# FT231X_Breakout.net
KiCad netlist of a schematic drawn in EAGLE
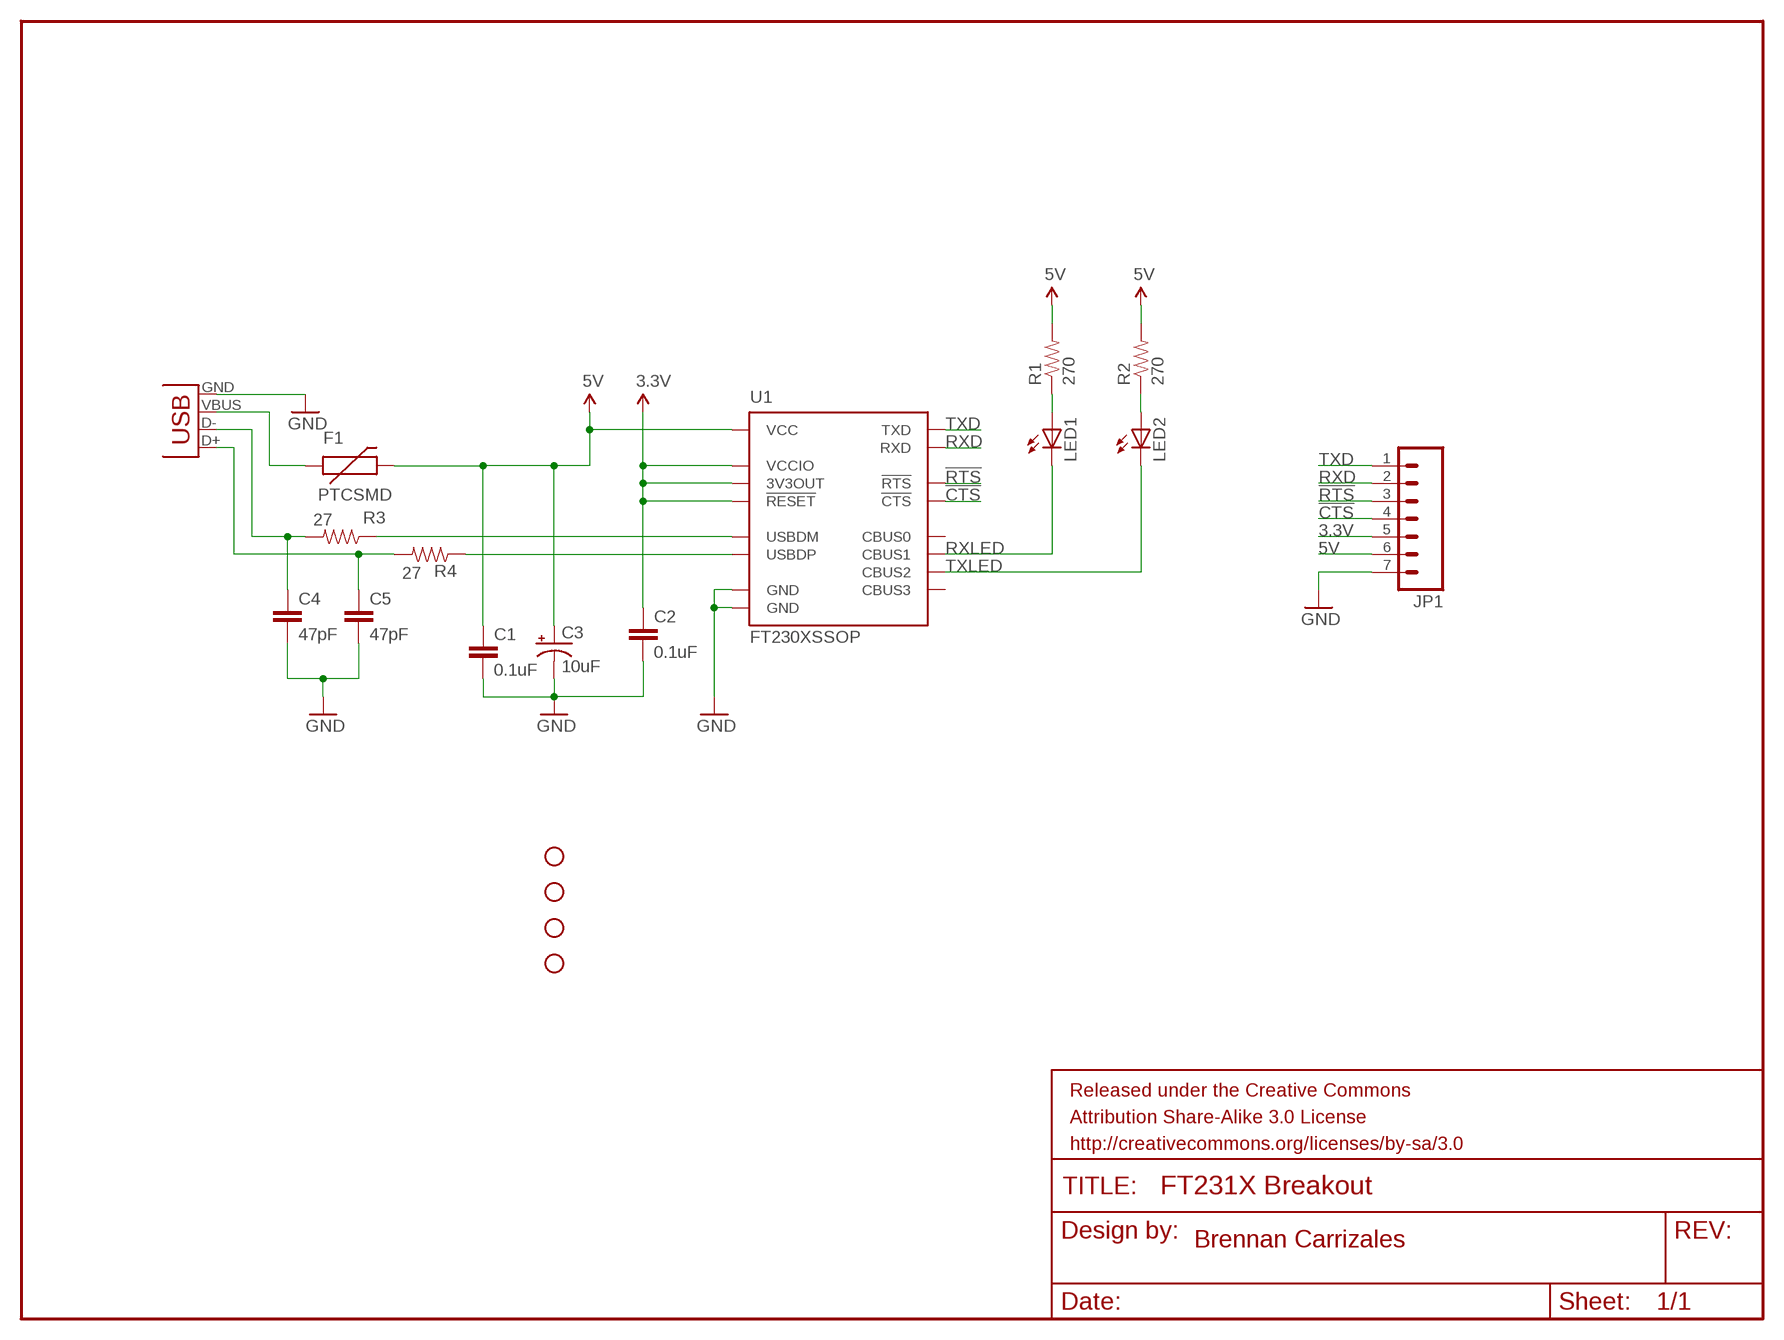
[diagram p0: schematic, sheet 1]

(export (version "E")
  (design (tool "Eeschema 10.0.6"))
  (components
    (comp (ref "C1")
      (value "0.1uF")
      (footprint "eagle-import:0603-CAP")
      (libsource (lib "eagle-import") (part "CAP0603-CAP"))
    )
    (comp (ref "C2")
      (value "0.1uF")
      (footprint "eagle-import:0603-CAP")
      (libsource (lib "eagle-import") (part "CAP0603-CAP"))
    )
    (comp (ref "C3")
      (value "10uF")
      (footprint "eagle-import:EIA3216-KIT")
      (libsource (lib "eagle-import") (part "CAP_POL1206-KIT"))
    )
    (comp (ref "C4")
      (value "47pF")
      (footprint "eagle-import:0603-CAP")
      (libsource (lib "eagle-import") (part "CAP0603-CAP"))
    )
    (comp (ref "C5")
      (value "47pF")
      (footprint "eagle-import:0603-CAP")
      (libsource (lib "eagle-import") (part "CAP0603-CAP"))
    )
    (comp (ref "F1")
      (value "PTCSMD")
      (footprint "eagle-import:PTC-1206")
      (libsource (lib "eagle-import") (part "PTCSMD"))
    )
    (comp (ref "FRAME1")
      (value "FRAME-LETTER")
      (footprint "eagle-import:CREATIVE_COMMONS")
      (libsource (lib "eagle-import") (part "FRAME-LETTER"))
    )
    (comp (ref "JP1")
      (value "M07")
      (footprint "eagle-import:1X07")
      (libsource (lib "eagle-import") (part "M07"))
    )
    (comp (ref "JP2")
      (value "USBSMD")
      (footprint "eagle-import:USB-MINIB")
      (libsource (lib "eagle-import") (part "USBSMD"))
    )
    (comp (ref "LED1")
      (value "LED0603")
      (footprint "eagle-import:LED-0603")
      (libsource (lib "eagle-import") (part "LED0603"))
    )
    (comp (ref "LED2")
      (value "LED0603")
      (footprint "eagle-import:LED-0603")
      (libsource (lib "eagle-import") (part "LED0603"))
    )
    (comp (ref "R1")
      (value "270")
      (footprint "eagle-import:0603-RES")
      (libsource (lib "eagle-import") (part "RESISTOR0603-RES"))
    )
    (comp (ref "R2")
      (value "270")
      (footprint "eagle-import:0603-RES")
      (libsource (lib "eagle-import") (part "RESISTOR0603-RES"))
    )
    (comp (ref "R3")
      (value "27")
      (footprint "eagle-import:0603-RES")
      (libsource (lib "eagle-import") (part "RESISTOR0603-RES"))
    )
    (comp (ref "R4")
      (value "27")
      (footprint "eagle-import:0603-RES")
      (libsource (lib "eagle-import") (part "RESISTOR0603-RES"))
    )
    (comp (ref "STANDOFF1")
      (value "STAND-OFF")
      (footprint "eagle-import:STAND-OFF")
      (libsource (lib "eagle-import") (part "STAND-OFF"))
    )
    (comp (ref "STANDOFF2")
      (value "STAND-OFF")
      (footprint "eagle-import:STAND-OFF")
      (libsource (lib "eagle-import") (part "STAND-OFF"))
    )
    (comp (ref "STANDOFF3")
      (value "STAND-OFF")
      (footprint "eagle-import:STAND-OFF")
      (libsource (lib "eagle-import") (part "STAND-OFF"))
    )
    (comp (ref "STANDOFF4")
      (value "STAND-OFF")
      (footprint "eagle-import:STAND-OFF")
      (libsource (lib "eagle-import") (part "STAND-OFF"))
    )
    (comp (ref "U1")
      (value "FT230XSSOP")
      (footprint "eagle-import:SSOP16")
      (libsource (lib "eagle-import") (part "FT230XSSOP"))
    )
  )
  (nets
    (net (code "1") (name "/RXD") (class "Default")
      (node (ref "JP1") (pin "2") (pinfunction "2_2") (pintype "passive"))
      (node (ref "U1") (pin "4") (pinfunction "RXD_4") (pintype "input"))
    )
    (net (code "2") (name "/RXLED") (class "Default")
      (node (ref "LED1") (pin "C") (pinfunction "C_C") (pintype "passive"))
      (node (ref "U1") (pin "14") (pinfunction "CBUS1_14") (pintype "bidirectional"))
    )
    (net (code "3") (name "/TXD") (class "Default")
      (node (ref "JP1") (pin "1") (pinfunction "1_1") (pintype "passive"))
      (node (ref "U1") (pin "1") (pinfunction "TXD_1") (pintype "output"))
    )
    (net (code "4") (name "/TXLED") (class "Default")
      (node (ref "LED2") (pin "C") (pinfunction "C_C") (pintype "passive"))
      (node (ref "U1") (pin "7") (pinfunction "CBUS2_7") (pintype "bidirectional"))
    )
    (net (code "5") (name "/~{CTS}") (class "Default")
      (node (ref "JP1") (pin "4") (pinfunction "4_4") (pintype "passive"))
      (node (ref "U1") (pin "6") (pinfunction "~{CTS}_6") (pintype "input"))
    )
    (net (code "6") (name "/~{RTS}") (class "Default")
      (node (ref "JP1") (pin "3") (pinfunction "3_3") (pintype "passive"))
      (node (ref "U1") (pin "2") (pinfunction "~{RTS}_2") (pintype "output"))
    )
    (net (code "7") (name "3.3V") (class "Default")
      (node (ref "C2") (pin "1") (pinfunction "1_1") (pintype "passive"))
      (node (ref "JP1") (pin "5") (pinfunction "5_5") (pintype "passive"))
      (node (ref "U1") (pin "10") (pinfunction "3V3OUT_10") (pintype "power_in"))
      (node (ref "U1") (pin "11") (pinfunction "~{RESET}_11") (pintype "input"))
      (node (ref "U1") (pin "3") (pinfunction "VCCIO_3") (pintype "power_in"))
    )
    (net (code "8") (name "5V") (class "Default")
      (node (ref "C1") (pin "1") (pinfunction "1_1") (pintype "passive"))
      (node (ref "C3") (pin "A") (pinfunction "+_A") (pintype "passive"))
      (node (ref "F1") (pin "2") (pinfunction "2_2") (pintype "bidirectional"))
      (node (ref "JP1") (pin "6") (pinfunction "6_6") (pintype "passive"))
      (node (ref "R1") (pin "2") (pinfunction "2_2") (pintype "passive"))
      (node (ref "R2") (pin "2") (pinfunction "2_2") (pintype "passive"))
      (node (ref "U1") (pin "12") (pinfunction "VCC_12") (pintype "power_in"))
    )
    (net (code "9") (name "GND") (class "Default")
      (node (ref "C1") (pin "2") (pinfunction "2_2") (pintype "passive"))
      (node (ref "C2") (pin "2") (pinfunction "2_2") (pintype "passive"))
      (node (ref "C3") (pin "C") (pinfunction "-_C") (pintype "passive"))
      (node (ref "C4") (pin "2") (pinfunction "2_2") (pintype "passive"))
      (node (ref "C5") (pin "2") (pinfunction "2_2") (pintype "passive"))
      (node (ref "JP1") (pin "7") (pinfunction "7_7") (pintype "passive"))
      (node (ref "JP2") (pin "GND") (pinfunction "GND_GND") (pintype "bidirectional"))
      (node (ref "U1") (pin "13") (pinfunction "GND_13") (pintype "power_in"))
      (node (ref "U1") (pin "5") (pinfunction "GND_5") (pintype "power_in"))
    )
    (net (code "10") (name "Net-(C4-Pad1)") (class "Default")
      (node (ref "C4") (pin "1") (pinfunction "1_1") (pintype "passive"))
      (node (ref "JP2") (pin "D-") (pinfunction "D-_D-") (pintype "bidirectional"))
      (node (ref "R3") (pin "2") (pinfunction "2_2") (pintype "passive"))
    )
    (net (code "11") (name "Net-(C5-Pad1)") (class "Default")
      (node (ref "C5") (pin "1") (pinfunction "1_1") (pintype "passive"))
      (node (ref "JP2") (pin "D+") (pinfunction "D+_D+") (pintype "bidirectional"))
      (node (ref "R4") (pin "2") (pinfunction "2_2") (pintype "passive"))
    )
    (net (code "12") (name "Net-(F1-Pad1)") (class "Default")
      (node (ref "F1") (pin "1") (pinfunction "1_1") (pintype "bidirectional"))
      (node (ref "JP2") (pin "VBUS") (pinfunction "VBUS_VBUS") (pintype "bidirectional"))
    )
    (net (code "13") (name "Net-(LED1-PadA)") (class "Default")
      (node (ref "LED1") (pin "A") (pinfunction "A_A") (pintype "passive"))
      (node (ref "R1") (pin "1") (pinfunction "1_1") (pintype "passive"))
    )
    (net (code "14") (name "Net-(LED2-PadA)") (class "Default")
      (node (ref "LED2") (pin "A") (pinfunction "A_A") (pintype "passive"))
      (node (ref "R2") (pin "1") (pinfunction "1_1") (pintype "passive"))
    )
    (net (code "15") (name "Net-(U1-USBDM)") (class "Default")
      (node (ref "R3") (pin "1") (pinfunction "1_1") (pintype "passive"))
      (node (ref "U1") (pin "9") (pinfunction "USBDM_9") (pintype "input"))
    )
    (net (code "16") (name "Net-(U1-USBDP)") (class "Default")
      (node (ref "R4") (pin "1") (pinfunction "1_1") (pintype "passive"))
      (node (ref "U1") (pin "8") (pinfunction "USBDP_8") (pintype "input"))
    )
    (net (code "17") (name "unconnected-(U1-CBUS0-Pad15)") (class "Default")
      (node (ref "U1") (pin "15") (pinfunction "CBUS0_15") (pintype "bidirectional"))
    )
    (net (code "18") (name "unconnected-(U1-CBUS3-Pad16)") (class "Default")
      (node (ref "U1") (pin "16") (pinfunction "CBUS3_16") (pintype "bidirectional"))
    )
  )
)
